# ESP8266_adapter.net
KiCad netlist of a schematic drawn in EAGLE
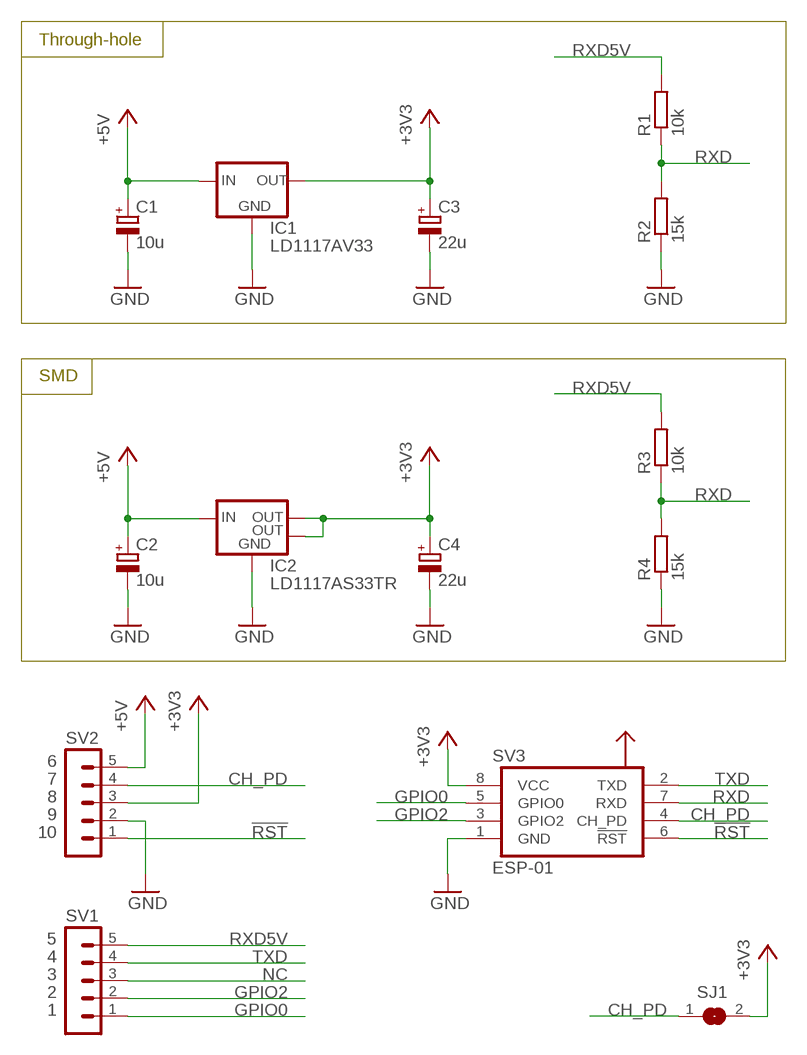
[diagram p0: schematic, sheet 1]

(export (version "E")
  (design (tool "Eeschema 10.0.6"))
  (components
    (comp (ref "C1")
      (value "10u")
      (footprint "eagle-import:E2,5-5")
      (libsource (lib "eagle-import") (part "CPOL-EUE2.5-5"))
    )
    (comp (ref "C2")
      (value "10u")
      (footprint "eagle-import:A_3216-18W")
      (libsource (lib "eagle-import") (part "CPOL-EUA/3216-18W"))
    )
    (comp (ref "C3")
      (value "22u")
      (footprint "eagle-import:E2,5-5")
      (libsource (lib "eagle-import") (part "CPOL-EUE2.5-5"))
    )
    (comp (ref "C4")
      (value "22u")
      (footprint "eagle-import:B_3528-21R")
      (libsource (lib "eagle-import") (part "CPOL-EUB/3528-21R"))
    )
    (comp (ref "IC1")
      (value "LD1117AV33")
      (footprint "eagle-import:78XXL")
      (libsource (lib "eagle-import") (part "V_REG_LD1117VXX"))
    )
    (comp (ref "IC2")
      (value "LD1117AS33TR")
      (footprint "eagle-import:SOT223")
      (libsource (lib "eagle-import") (part "V_REG_LM1117SOT223"))
    )
    (comp (ref "R1")
      (value "10k")
      (footprint "eagle-import:0207_10")
      (libsource (lib "eagle-import") (part "R-EU_0207/10"))
    )
    (comp (ref "R2")
      (value "15k")
      (footprint "eagle-import:0207_10")
      (libsource (lib "eagle-import") (part "R-EU_0207/10"))
    )
    (comp (ref "R3")
      (value "10k")
      (footprint "eagle-import:R1206")
      (libsource (lib "eagle-import") (part "R-EU_R1206"))
    )
    (comp (ref "R4")
      (value "15k")
      (footprint "eagle-import:R1206")
      (libsource (lib "eagle-import") (part "R-EU_R1206"))
    )
    (comp (ref "SJ1") (value "SJ") (footprint "eagle-import:SJ") (libsource (lib "eagle-import") (part "SJ")))
    (comp (ref "SV1")
      (value "MA05-1")
      (footprint "eagle-import:MA05-1")
      (libsource (lib "eagle-import") (part "MA05-1"))
    )
    (comp (ref "SV2")
      (value "MA05-1")
      (footprint "eagle-import:MA05-1")
      (libsource (lib "eagle-import") (part "MA05-1"))
    )
    (comp (ref "SV3")
      (value "ESP-01")
      (footprint "eagle-import:FE04-2")
      (libsource (lib "eagle-import") (part "ESP-01"))
    )
  )
  (nets
    (net (code "1") (name "+3V3") (class "Default")
      (node (ref "C3") (pin "+") (pinfunction "+_+") (pintype "passive"))
      (node (ref "C4") (pin "+") (pinfunction "+_+") (pintype "passive"))
      (node (ref "IC1") (pin "GND") (pinfunction "OUT_GND") (pintype "passive"))
      (node (ref "IC2") (pin "2") (pinfunction "OUT_2") (pintype "output"))
      (node (ref "IC2") (pin "4") (pinfunction "OUT_4") (pintype "output"))
      (node (ref "SJ1") (pin "2") (pinfunction "2_2") (pintype "passive"))
      (node (ref "SV2") (pin "3") (pinfunction "3_3") (pintype "passive"))
      (node (ref "SV3") (pin "8") (pinfunction "VCC_8") (pintype "passive"))
    )
    (net (code "2") (name "+5V") (class "Default")
      (node (ref "C1") (pin "+") (pinfunction "+_+") (pintype "passive"))
      (node (ref "C2") (pin "+") (pinfunction "+_+") (pintype "passive"))
      (node (ref "IC1") (pin "OUT") (pinfunction "IN_OUT") (pintype "input"))
      (node (ref "IC2") (pin "3") (pinfunction "IN_3") (pintype "input"))
      (node (ref "SV2") (pin "5") (pinfunction "5_5") (pintype "passive"))
    )
    (net (code "3") (name "/CH_PD") (class "Default")
      (node (ref "SJ1") (pin "1") (pinfunction "1_1") (pintype "passive"))
      (node (ref "SV2") (pin "4") (pinfunction "4_4") (pintype "passive"))
      (node (ref "SV3") (pin "4") (pinfunction "CH_PD_4") (pintype "passive"))
    )
    (net (code "4") (name "/GPIO0") (class "Default")
      (node (ref "SV1") (pin "1") (pinfunction "1_1") (pintype "passive"))
      (node (ref "SV3") (pin "5") (pinfunction "GPIO0_5") (pintype "passive"))
    )
    (net (code "5") (name "/GPIO2") (class "Default")
      (node (ref "SV1") (pin "2") (pinfunction "2_2") (pintype "passive"))
      (node (ref "SV3") (pin "3") (pinfunction "GPIO2_3") (pintype "passive"))
    )
    (net (code "6") (name "/NC") (class "Default")
      (node (ref "SV1") (pin "3") (pinfunction "3_3") (pintype "passive"))
    )
    (net (code "7") (name "/RXD") (class "Default")
      (node (ref "R1") (pin "1") (pinfunction "1_1") (pintype "passive"))
      (node (ref "R2") (pin "2") (pinfunction "2_2") (pintype "passive"))
      (node (ref "R3") (pin "1") (pinfunction "1_1") (pintype "passive"))
      (node (ref "R4") (pin "2") (pinfunction "2_2") (pintype "passive"))
      (node (ref "SV3") (pin "7") (pinfunction "RXD_7") (pintype "passive"))
    )
    (net (code "8") (name "/RXD5V") (class "Default")
      (node (ref "R1") (pin "2") (pinfunction "2_2") (pintype "passive"))
      (node (ref "R3") (pin "2") (pinfunction "2_2") (pintype "passive"))
      (node (ref "SV1") (pin "5") (pinfunction "5_5") (pintype "passive"))
    )
    (net (code "9") (name "/TXD") (class "Default")
      (node (ref "SV1") (pin "4") (pinfunction "4_4") (pintype "passive"))
      (node (ref "SV3") (pin "2") (pinfunction "TXD_2") (pintype "passive"))
    )
    (net (code "10") (name "/~{RST}") (class "Default")
      (node (ref "SV2") (pin "1") (pinfunction "1_1") (pintype "passive"))
      (node (ref "SV3") (pin "6") (pinfunction "~{RST}_6") (pintype "passive"))
    )
    (net (code "11") (name "GND") (class "Default")
      (node (ref "C1") (pin "-") (pinfunction "-_-") (pintype "passive"))
      (node (ref "C2") (pin "-") (pinfunction "-_-") (pintype "passive"))
      (node (ref "C3") (pin "-") (pinfunction "-_-") (pintype "passive"))
      (node (ref "C4") (pin "-") (pinfunction "-_-") (pintype "passive"))
      (node (ref "IC1") (pin "IN") (pinfunction "GND_IN") (pintype "input"))
      (node (ref "IC2") (pin "1") (pinfunction "GND_1") (pintype "input"))
      (node (ref "R2") (pin "1") (pinfunction "1_1") (pintype "passive"))
      (node (ref "R4") (pin "1") (pinfunction "1_1") (pintype "passive"))
      (node (ref "SV2") (pin "2") (pinfunction "2_2") (pintype "passive"))
      (node (ref "SV3") (pin "1") (pinfunction "GND_1") (pintype "passive"))
    )
  )
)
